# LCD-BackPack_v11.net
KiCad netlist of a schematic drawn in EAGLE
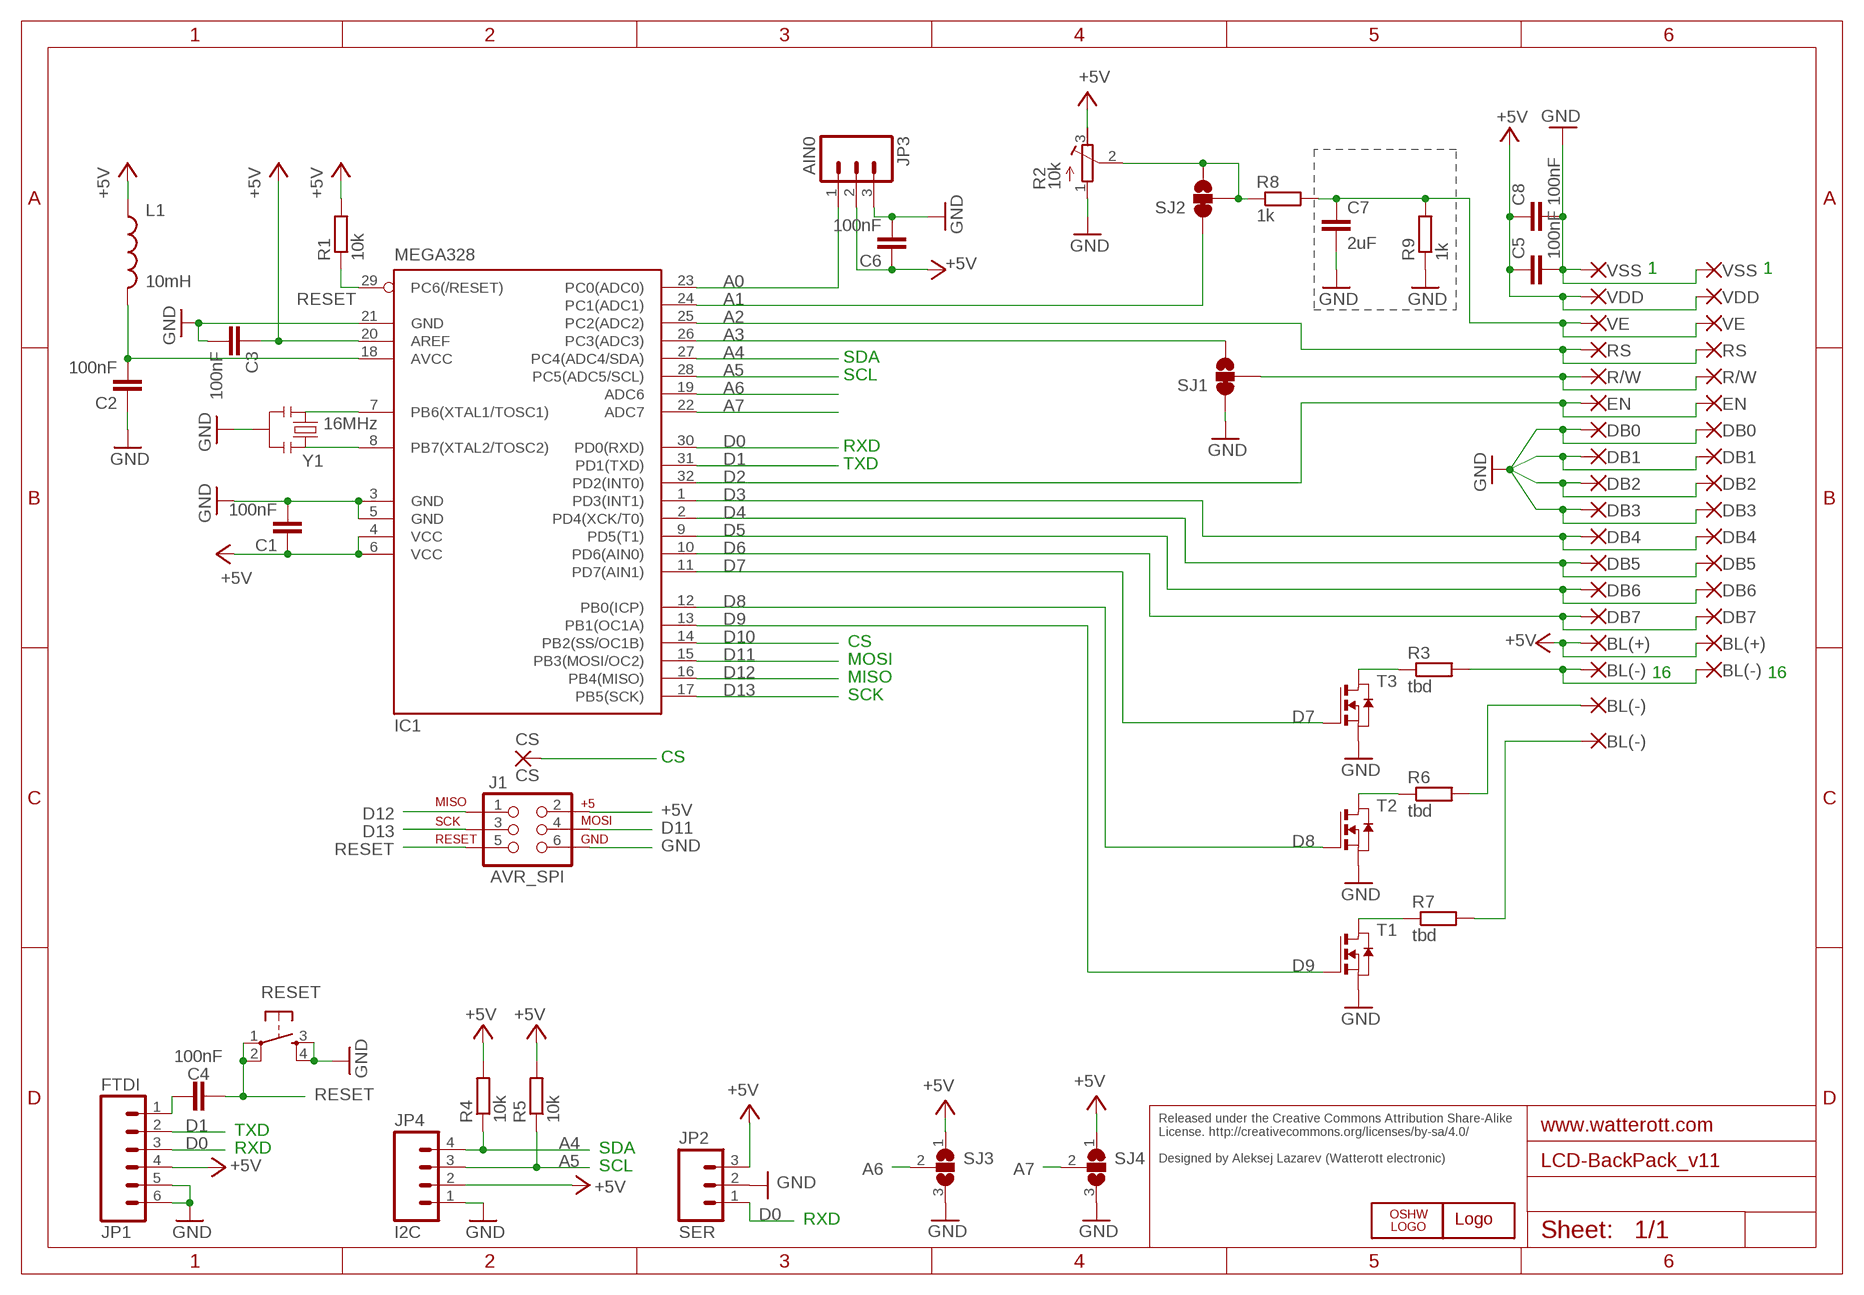
[diagram p0: schematic, sheet 1]

(export (version "E")
  (design (tool "Eeschema 10.0.6"))
  (components
    (comp (ref "C1")
      (value "100nF")
      (footprint "eagle-import:C0603")
      (libsource (lib "eagle-import") (part "C-EUC0603"))
    )
    (comp (ref "C2")
      (value "100nF")
      (footprint "eagle-import:C0603")
      (libsource (lib "eagle-import") (part "C-EUC0603"))
    )
    (comp (ref "C3")
      (value "100nF")
      (footprint "eagle-import:C0603")
      (libsource (lib "eagle-import") (part "C-EUC0603"))
    )
    (comp (ref "C4")
      (value "100nF")
      (footprint "eagle-import:C0603")
      (libsource (lib "eagle-import") (part "C-EUC0603"))
    )
    (comp (ref "C5")
      (value "100nF")
      (footprint "eagle-import:C0603")
      (libsource (lib "eagle-import") (part "C-EUC0603"))
    )
    (comp (ref "C6")
      (value "100nF")
      (footprint "eagle-import:C0603")
      (libsource (lib "eagle-import") (part "C-EUC0603"))
    )
    (comp (ref "C7")
      (value "2uF")
      (footprint "eagle-import:C0603")
      (libsource (lib "eagle-import") (part "C-EUC0603"))
    )
    (comp (ref "C8")
      (value "100nF")
      (footprint "eagle-import:C0603")
      (libsource (lib "eagle-import") (part "C-EUC0603"))
    )
    (comp (ref "CS")
      (value "CS")
      (footprint "eagle-import:1,6_0,9")
      (libsource (lib "eagle-import") (part "1,6/0,9"))
    )
    (comp (ref "IC1")
      (value "MEGA328")
      (footprint "eagle-import:TQFP32-08")
      (fields (field (name "MPN") "ATMEGA8-16AU"))
      (libsource (lib "eagle-import") (part "MEGA8-AI"))
    )
    (comp (ref "J1")
      (value "AVR_SPI")
      (footprint "eagle-import:2X3")
      (libsource (lib "eagle-import") (part "AVR_SPI_PRG_6PTH"))
    )
    (comp (ref "JP1")
      (value "FTDI")
      (footprint "eagle-import:1X06")
      (libsource (lib "eagle-import") (part "M06SIP"))
    )
    (comp (ref "JP2")
      (value "SER")
      (footprint "eagle-import:1X03")
      (libsource (lib "eagle-import") (part "M03PTH"))
    )
    (comp (ref "JP3")
      (value "AIN0")
      (footprint "eagle-import:1X03")
      (libsource (lib "eagle-import") (part "M03PTH"))
    )
    (comp (ref "JP4")
      (value "I2C")
      (footprint "eagle-import:1X04")
      (libsource (lib "eagle-import") (part "M04PTH"))
    )
    (comp (ref "L1")
      (value "10mH")
      (footprint "eagle-import:0603")
      (libsource (lib "eagle-import") (part "INDUCTOR30OHM,1.8A"))
    )
    (comp (ref "LOGO1")
      (value "OSHW_LOGO_6MILX0150-NT")
      (footprint "eagle-import:OSHW_6X150_NOTEXT")
      (libsource (lib "eagle-import") (part "OSHW_LOGO_6MILX0150-NT"))
    )
    (comp (ref "P1")
      (value "VSS")
      (footprint "eagle-import:1,6_0,9")
      (libsource (lib "eagle-import") (part "1,6/0,9"))
    )
    (comp (ref "P2")
      (value "VDD")
      (footprint "eagle-import:1,6_0,9")
      (libsource (lib "eagle-import") (part "1,6/0,9"))
    )
    (comp (ref "P3")
      (value "VE")
      (footprint "eagle-import:1,6_0,9")
      (libsource (lib "eagle-import") (part "1,6/0,9"))
    )
    (comp (ref "P4")
      (value "RS")
      (footprint "eagle-import:1,6_0,9")
      (libsource (lib "eagle-import") (part "1,6/0,9"))
    )
    (comp (ref "P5")
      (value "R/W")
      (footprint "eagle-import:1,6_0,9")
      (libsource (lib "eagle-import") (part "1,6/0,9"))
    )
    (comp (ref "P6")
      (value "EN")
      (footprint "eagle-import:1,6_0,9")
      (libsource (lib "eagle-import") (part "1,6/0,9"))
    )
    (comp (ref "P7")
      (value "DB0")
      (footprint "eagle-import:1,6_0,9")
      (libsource (lib "eagle-import") (part "1,6/0,9"))
    )
    (comp (ref "P8")
      (value "DB1")
      (footprint "eagle-import:1,6_0,9")
      (libsource (lib "eagle-import") (part "1,6/0,9"))
    )
    (comp (ref "P9")
      (value "DB2")
      (footprint "eagle-import:1,6_0,9")
      (libsource (lib "eagle-import") (part "1,6/0,9"))
    )
    (comp (ref "P10")
      (value "DB3")
      (footprint "eagle-import:1,6_0,9")
      (libsource (lib "eagle-import") (part "1,6/0,9"))
    )
    (comp (ref "P11")
      (value "DB4")
      (footprint "eagle-import:1,6_0,9")
      (libsource (lib "eagle-import") (part "1,6/0,9"))
    )
    (comp (ref "P12")
      (value "DB5")
      (footprint "eagle-import:1,6_0,9")
      (libsource (lib "eagle-import") (part "1,6/0,9"))
    )
    (comp (ref "P13")
      (value "DB6")
      (footprint "eagle-import:1,6_0,9")
      (libsource (lib "eagle-import") (part "1,6/0,9"))
    )
    (comp (ref "P14")
      (value "DB7")
      (footprint "eagle-import:1,6_0,9")
      (libsource (lib "eagle-import") (part "1,6/0,9"))
    )
    (comp (ref "P15")
      (value "BL(+)")
      (footprint "eagle-import:1,6_0,9")
      (libsource (lib "eagle-import") (part "1,6/0,9"))
    )
    (comp (ref "P16")
      (value "BL(-)")
      (footprint "eagle-import:1,6_0,9")
      (libsource (lib "eagle-import") (part "1,6/0,9"))
    )
    (comp (ref "P17")
      (value "BL(-)")
      (footprint "eagle-import:1,6_0,9")
      (libsource (lib "eagle-import") (part "1,6/0,9"))
    )
    (comp (ref "P18")
      (value "BL(-)")
      (footprint "eagle-import:1,6_0,9")
      (libsource (lib "eagle-import") (part "1,6/0,9"))
    )
    (comp (ref "P19")
      (value "VSS")
      (footprint "eagle-import:1,6_0,9")
      (libsource (lib "eagle-import") (part "1,6/0,9"))
    )
    (comp (ref "P20")
      (value "VDD")
      (footprint "eagle-import:1,6_0,9")
      (libsource (lib "eagle-import") (part "1,6/0,9"))
    )
    (comp (ref "P21")
      (value "VE")
      (footprint "eagle-import:1,6_0,9")
      (libsource (lib "eagle-import") (part "1,6/0,9"))
    )
    (comp (ref "P22")
      (value "RS")
      (footprint "eagle-import:1,6_0,9")
      (libsource (lib "eagle-import") (part "1,6/0,9"))
    )
    (comp (ref "P23")
      (value "R/W")
      (footprint "eagle-import:1,6_0,9")
      (libsource (lib "eagle-import") (part "1,6/0,9"))
    )
    (comp (ref "P24")
      (value "EN")
      (footprint "eagle-import:1,6_0,9")
      (libsource (lib "eagle-import") (part "1,6/0,9"))
    )
    (comp (ref "P25")
      (value "DB0")
      (footprint "eagle-import:1,6_0,9")
      (libsource (lib "eagle-import") (part "1,6/0,9"))
    )
    (comp (ref "P26")
      (value "DB1")
      (footprint "eagle-import:1,6_0,9")
      (libsource (lib "eagle-import") (part "1,6/0,9"))
    )
    (comp (ref "P27")
      (value "DB2")
      (footprint "eagle-import:1,6_0,9")
      (libsource (lib "eagle-import") (part "1,6/0,9"))
    )
    (comp (ref "P28")
      (value "DB3")
      (footprint "eagle-import:1,6_0,9")
      (libsource (lib "eagle-import") (part "1,6/0,9"))
    )
    (comp (ref "P29")
      (value "DB4")
      (footprint "eagle-import:1,6_0,9")
      (libsource (lib "eagle-import") (part "1,6/0,9"))
    )
    (comp (ref "P30")
      (value "DB5")
      (footprint "eagle-import:1,6_0,9")
      (libsource (lib "eagle-import") (part "1,6/0,9"))
    )
    (comp (ref "P31")
      (value "DB6")
      (footprint "eagle-import:1,6_0,9")
      (libsource (lib "eagle-import") (part "1,6/0,9"))
    )
    (comp (ref "P32")
      (value "DB7")
      (footprint "eagle-import:1,6_0,9")
      (libsource (lib "eagle-import") (part "1,6/0,9"))
    )
    (comp (ref "P33")
      (value "BL(+)")
      (footprint "eagle-import:1,6_0,9")
      (libsource (lib "eagle-import") (part "1,6/0,9"))
    )
    (comp (ref "P34")
      (value "BL(-)")
      (footprint "eagle-import:1,6_0,9")
      (libsource (lib "eagle-import") (part "1,6/0,9"))
    )
    (comp (ref "R1")
      (value "10k")
      (footprint "eagle-import:R0603")
      (libsource (lib "eagle-import") (part "R-EU_R0603"))
    )
    (comp (ref "R2")
      (value "10k")
      (footprint "eagle-import:RTRIM3374")
      (libsource (lib "eagle-import") (part "R-TRIMM3374"))
    )
    (comp (ref "R3")
      (value "tbd")
      (footprint "eagle-import:R0603")
      (libsource (lib "eagle-import") (part "R-EU_R0603"))
    )
    (comp (ref "R4")
      (value "10k")
      (footprint "eagle-import:R0603")
      (libsource (lib "eagle-import") (part "R-EU_R0603"))
    )
    (comp (ref "R5")
      (value "10k")
      (footprint "eagle-import:R0603")
      (libsource (lib "eagle-import") (part "R-EU_R0603"))
    )
    (comp (ref "R6")
      (value "tbd")
      (footprint "eagle-import:R0603")
      (libsource (lib "eagle-import") (part "R-EU_R0603"))
    )
    (comp (ref "R7")
      (value "tbd")
      (footprint "eagle-import:R0603")
      (libsource (lib "eagle-import") (part "R-EU_R0603"))
    )
    (comp (ref "R8")
      (value "1k")
      (footprint "eagle-import:R0603")
      (libsource (lib "eagle-import") (part "R-EU_R0603"))
    )
    (comp (ref "R9")
      (value "1k")
      (footprint "eagle-import:R0603")
      (libsource (lib "eagle-import") (part "R-EU_R0603"))
    )
    (comp (ref "RESET")
      (value "TAC_SWITCHSMD")
      (footprint "eagle-import:TACTILE_SWITCH_SMD")
      (libsource (lib "eagle-import") (part "TAC_SWITCHSMD"))
    )
    (comp (ref "SJ1")
      (value "SOLDERJUMPER_2WAY-OLDS")
      (footprint "eagle-import:SJ_3")
      (libsource (lib "eagle-import") (part "SOLDERJUMPER_2WAY-OLDS"))
    )
    (comp (ref "SJ2")
      (value "SOLDERJUMPER_2WAY-OLDS")
      (footprint "eagle-import:SJ_3")
      (libsource (lib "eagle-import") (part "SOLDERJUMPER_2WAY-OLDS"))
    )
    (comp (ref "SJ3")
      (value "SJ2W")
      (footprint "eagle-import:SJ_2")
      (libsource (lib "eagle-import") (part "SJ2W"))
    )
    (comp (ref "SJ4")
      (value "SJ2W")
      (footprint "eagle-import:SJ_2")
      (libsource (lib "eagle-import") (part "SJ2W"))
    )
    (comp (ref "T1")
      (value "NMOSSOT23")
      (footprint "eagle-import:SOT-23")
      (libsource (lib "eagle-import") (part "NMOSSOT23"))
    )
    (comp (ref "T2")
      (value "NMOSSOT23")
      (footprint "eagle-import:SOT-23")
      (libsource (lib "eagle-import") (part "NMOSSOT23"))
    )
    (comp (ref "T3")
      (value "NMOSSOT23")
      (footprint "eagle-import:SOT-23")
      (libsource (lib "eagle-import") (part "NMOSSOT23"))
    )
    (comp (ref "U$1")
      (value "WE-LOGO")
      (footprint "eagle-import:WE-LOGO")
      (libsource (lib "eagle-import") (part "WE-LOGOPLACE"))
    )
    (comp (ref "Y1")
      (value "16MHz")
      (footprint "eagle-import:RESONATOR-SMD")
      (libsource (lib "eagle-import") (part "RESONATOR16MHZ"))
    )
  )
  (nets
    (net (code "1") (name "+5V") (class "Default")
      (node (ref "C1") (pin "1") (pinfunction "1_1") (pintype "passive"))
      (node (ref "C3") (pin "1") (pinfunction "1_1") (pintype "passive"))
      (node (ref "C5") (pin "1") (pinfunction "1_1") (pintype "passive"))
      (node (ref "C6") (pin "1") (pinfunction "1_1") (pintype "passive"))
      (node (ref "C8") (pin "1") (pinfunction "1_1") (pintype "passive"))
      (node (ref "IC1") (pin "20") (pinfunction "AREF_20") (pintype "passive"))
      (node (ref "IC1") (pin "4") (pinfunction "VCC_4") (pintype "power_in"))
      (node (ref "IC1") (pin "6") (pinfunction "VCC_6") (pintype "power_in"))
      (node (ref "J1") (pin "2") (pinfunction "2_2") (pintype "passive"))
      (node (ref "JP1") (pin "4") (pinfunction "4_4") (pintype "passive"))
      (node (ref "JP2") (pin "3") (pinfunction "3_3") (pintype "passive"))
      (node (ref "JP3") (pin "2") (pinfunction "2_2") (pintype "passive"))
      (node (ref "JP4") (pin "2") (pinfunction "2_2") (pintype "passive"))
      (node (ref "L1") (pin "1") (pinfunction "1_1") (pintype "passive"))
      (node (ref "P15") (pin "1") (pinfunction "P_1") (pintype "passive"))
      (node (ref "P2") (pin "1") (pinfunction "P_1") (pintype "passive"))
      (node (ref "P20") (pin "1") (pinfunction "P_1") (pintype "passive"))
      (node (ref "P33") (pin "1") (pinfunction "P_1") (pintype "passive"))
      (node (ref "R1") (pin "2") (pinfunction "2_2") (pintype "passive"))
      (node (ref "R2") (pin "3") (pinfunction "A_3") (pintype "passive"))
      (node (ref "R4") (pin "2") (pinfunction "2_2") (pintype "passive"))
      (node (ref "R5") (pin "2") (pinfunction "2_2") (pintype "passive"))
      (node (ref "SJ3") (pin "1") (pinfunction "1_1") (pintype "passive"))
      (node (ref "SJ4") (pin "1") (pinfunction "1_1") (pintype "passive"))
    )
    (net (code "2") (name "/A0") (class "Default")
      (node (ref "IC1") (pin "23") (pinfunction "PC0(ADC0)_23") (pintype "bidirectional"))
      (node (ref "JP3") (pin "1") (pinfunction "1_1") (pintype "passive"))
    )
    (net (code "3") (name "/A1") (class "Default")
      (node (ref "IC1") (pin "24") (pinfunction "PC1(ADC1)_24") (pintype "bidirectional"))
      (node (ref "SJ2") (pin "1") (pinfunction "1_1") (pintype "passive"))
    )
    (net (code "4") (name "/A2") (class "Default")
      (node (ref "IC1") (pin "25") (pinfunction "PC2(ADC2)_25") (pintype "bidirectional"))
      (node (ref "P22") (pin "1") (pinfunction "P_1") (pintype "passive"))
      (node (ref "P4") (pin "1") (pinfunction "P_1") (pintype "passive"))
    )
    (net (code "5") (name "/A3") (class "Default")
      (node (ref "IC1") (pin "26") (pinfunction "PC3(ADC3)_26") (pintype "bidirectional"))
      (node (ref "SJ1") (pin "3") (pinfunction "3_3") (pintype "passive"))
    )
    (net (code "6") (name "/A4") (class "Default")
      (node (ref "IC1") (pin "27") (pinfunction "PC4(ADC4/SDA)_27") (pintype "bidirectional"))
      (node (ref "JP4") (pin "4") (pinfunction "4_4") (pintype "passive"))
      (node (ref "R4") (pin "1") (pinfunction "1_1") (pintype "passive"))
    )
    (net (code "7") (name "/A5") (class "Default")
      (node (ref "IC1") (pin "28") (pinfunction "PC5(ADC5/SCL)_28") (pintype "bidirectional"))
      (node (ref "JP4") (pin "3") (pinfunction "3_3") (pintype "passive"))
      (node (ref "R5") (pin "1") (pinfunction "1_1") (pintype "passive"))
    )
    (net (code "8") (name "/A6") (class "Default")
      (node (ref "IC1") (pin "19") (pinfunction "ADC6_19") (pintype "bidirectional"))
      (node (ref "SJ3") (pin "2") (pinfunction "2_2") (pintype "passive"))
    )
    (net (code "9") (name "/A7") (class "Default")
      (node (ref "IC1") (pin "22") (pinfunction "ADC7_22") (pintype "bidirectional"))
      (node (ref "SJ4") (pin "2") (pinfunction "2_2") (pintype "passive"))
    )
    (net (code "10") (name "/D0") (class "Default")
      (node (ref "IC1") (pin "30") (pinfunction "PD0(RXD)_30") (pintype "bidirectional"))
      (node (ref "JP1") (pin "3") (pinfunction "3_3") (pintype "passive"))
      (node (ref "JP2") (pin "1") (pinfunction "1_1") (pintype "passive"))
    )
    (net (code "11") (name "/D1") (class "Default")
      (node (ref "IC1") (pin "31") (pinfunction "PD1(TXD)_31") (pintype "bidirectional"))
      (node (ref "JP1") (pin "2") (pinfunction "2_2") (pintype "passive"))
    )
    (net (code "12") (name "/D2") (class "Default")
      (node (ref "IC1") (pin "32") (pinfunction "PD2(INT0)_32") (pintype "bidirectional"))
      (node (ref "P24") (pin "1") (pinfunction "P_1") (pintype "passive"))
      (node (ref "P6") (pin "1") (pinfunction "P_1") (pintype "passive"))
    )
    (net (code "13") (name "/D3") (class "Default")
      (node (ref "IC1") (pin "1") (pinfunction "PD3(INT1)_1") (pintype "bidirectional"))
      (node (ref "P11") (pin "1") (pinfunction "P_1") (pintype "passive"))
      (node (ref "P29") (pin "1") (pinfunction "P_1") (pintype "passive"))
    )
    (net (code "14") (name "/D4") (class "Default")
      (node (ref "IC1") (pin "2") (pinfunction "PD4(XCK/T0)_2") (pintype "bidirectional"))
      (node (ref "P12") (pin "1") (pinfunction "P_1") (pintype "passive"))
      (node (ref "P30") (pin "1") (pinfunction "P_1") (pintype "passive"))
    )
    (net (code "15") (name "/D5") (class "Default")
      (node (ref "IC1") (pin "9") (pinfunction "PD5(T1)_9") (pintype "bidirectional"))
      (node (ref "P13") (pin "1") (pinfunction "P_1") (pintype "passive"))
      (node (ref "P31") (pin "1") (pinfunction "P_1") (pintype "passive"))
    )
    (net (code "16") (name "/D6") (class "Default")
      (node (ref "IC1") (pin "10") (pinfunction "PD6(AIN0)_10") (pintype "bidirectional"))
      (node (ref "P14") (pin "1") (pinfunction "P_1") (pintype "passive"))
      (node (ref "P32") (pin "1") (pinfunction "P_1") (pintype "passive"))
    )
    (net (code "17") (name "/D7") (class "Default")
      (node (ref "IC1") (pin "11") (pinfunction "PD7(AIN1)_11") (pintype "bidirectional"))
      (node (ref "T3") (pin "3") (pinfunction "G_3") (pintype "passive"))
    )
    (net (code "18") (name "/D8") (class "Default")
      (node (ref "IC1") (pin "12") (pinfunction "PB0(ICP)_12") (pintype "bidirectional"))
      (node (ref "T2") (pin "3") (pinfunction "G_3") (pintype "passive"))
    )
    (net (code "19") (name "/D9") (class "Default")
      (node (ref "IC1") (pin "13") (pinfunction "PB1(OC1A)_13") (pintype "bidirectional"))
      (node (ref "T1") (pin "3") (pinfunction "G_3") (pintype "passive"))
    )
    (net (code "20") (name "/D10") (class "Default")
      (node (ref "CS") (pin "1") (pinfunction "P_1") (pintype "passive"))
      (node (ref "IC1") (pin "14") (pinfunction "PB2(SS/OC1B)_14") (pintype "bidirectional"))
    )
    (net (code "21") (name "/D11") (class "Default")
      (node (ref "IC1") (pin "15") (pinfunction "PB3(MOSI/OC2)_15") (pintype "bidirectional"))
      (node (ref "J1") (pin "4") (pinfunction "4_4") (pintype "passive"))
    )
    (net (code "22") (name "/D12") (class "Default")
      (node (ref "IC1") (pin "16") (pinfunction "PB4(MISO)_16") (pintype "bidirectional"))
      (node (ref "J1") (pin "1") (pinfunction "1_1") (pintype "passive"))
    )
    (net (code "23") (name "/D13") (class "Default")
      (node (ref "IC1") (pin "17") (pinfunction "PB5(SCK)_17") (pintype "bidirectional"))
      (node (ref "J1") (pin "3") (pinfunction "3_3") (pintype "passive"))
    )
    (net (code "24") (name "/RESET") (class "Default")
      (node (ref "C4") (pin "1") (pinfunction "1_1") (pintype "passive"))
      (node (ref "IC1") (pin "29") (pinfunction "PC6(/RESET)_29") (pintype "bidirectional"))
      (node (ref "J1") (pin "5") (pinfunction "5_5") (pintype "passive"))
      (node (ref "R1") (pin "1") (pinfunction "1_1") (pintype "passive"))
      (node (ref "RESET") (pin "1") (pinfunction "1_1") (pintype "passive"))
      (node (ref "RESET") (pin "2") (pinfunction "2_2") (pintype "passive"))
    )
    (net (code "25") (name "GND") (class "Default")
      (node (ref "C1") (pin "2") (pinfunction "2_2") (pintype "passive"))
      (node (ref "C2") (pin "1") (pinfunction "1_1") (pintype "passive"))
      (node (ref "C3") (pin "2") (pinfunction "2_2") (pintype "passive"))
      (node (ref "C5") (pin "2") (pinfunction "2_2") (pintype "passive"))
      (node (ref "C6") (pin "2") (pinfunction "2_2") (pintype "passive"))
      (node (ref "C7") (pin "2") (pinfunction "2_2") (pintype "passive"))
      (node (ref "C8") (pin "2") (pinfunction "2_2") (pintype "passive"))
      (node (ref "IC1") (pin "21") (pinfunction "GND_21") (pintype "power_in"))
      (node (ref "IC1") (pin "3") (pinfunction "GND_3") (pintype "power_in"))
      (node (ref "IC1") (pin "5") (pinfunction "GND_5") (pintype "power_in"))
      (node (ref "J1") (pin "6") (pinfunction "6_6") (pintype "passive"))
      (node (ref "JP1") (pin "5") (pinfunction "5_5") (pintype "passive"))
      (node (ref "JP1") (pin "6") (pinfunction "6_6") (pintype "passive"))
      (node (ref "JP2") (pin "2") (pinfunction "2_2") (pintype "passive"))
      (node (ref "JP3") (pin "3") (pinfunction "3_3") (pintype "passive"))
      (node (ref "JP4") (pin "1") (pinfunction "1_1") (pintype "passive"))
      (node (ref "P1") (pin "1") (pinfunction "P_1") (pintype "passive"))
      (node (ref "P10") (pin "1") (pinfunction "P_1") (pintype "passive"))
      (node (ref "P19") (pin "1") (pinfunction "P_1") (pintype "passive"))
      (node (ref "P25") (pin "1") (pinfunction "P_1") (pintype "passive"))
      (node (ref "P26") (pin "1") (pinfunction "P_1") (pintype "passive"))
      (node (ref "P27") (pin "1") (pinfunction "P_1") (pintype "passive"))
      (node (ref "P28") (pin "1") (pinfunction "P_1") (pintype "passive"))
      (node (ref "P7") (pin "1") (pinfunction "P_1") (pintype "passive"))
      (node (ref "P8") (pin "1") (pinfunction "P_1") (pintype "passive"))
      (node (ref "P9") (pin "1") (pinfunction "P_1") (pintype "passive"))
      (node (ref "R2") (pin "1") (pinfunction "E_1") (pintype "passive"))
      (node (ref "R9") (pin "1") (pinfunction "1_1") (pintype "passive"))
      (node (ref "RESET") (pin "3") (pinfunction "3_3") (pintype "passive"))
      (node (ref "RESET") (pin "4") (pinfunction "4_4") (pintype "passive"))
      (node (ref "SJ1") (pin "1") (pinfunction "1_1") (pintype "passive"))
      (node (ref "SJ3") (pin "3") (pinfunction "3_3") (pintype "passive"))
      (node (ref "SJ4") (pin "3") (pinfunction "3_3") (pintype "passive"))
      (node (ref "T1") (pin "2") (pinfunction "S_2") (pintype "passive"))
      (node (ref "T2") (pin "2") (pinfunction "S_2") (pintype "passive"))
      (node (ref "T3") (pin "2") (pinfunction "S_2") (pintype "passive"))
      (node (ref "Y1") (pin "2") (pinfunction "2_2") (pintype "passive"))
    )
    (net (code "26") (name "Net-(C4-Pad2)") (class "Default")
      (node (ref "C4") (pin "2") (pinfunction "2_2") (pintype "passive"))
      (node (ref "JP1") (pin "1") (pinfunction "1_1") (pintype "passive"))
    )
    (net (code "27") (name "Net-(IC1-AVCC)") (class "Default")
      (node (ref "C2") (pin "2") (pinfunction "2_2") (pintype "passive"))
      (node (ref "IC1") (pin "18") (pinfunction "AVCC_18") (pintype "power_in"))
      (node (ref "L1") (pin "2") (pinfunction "2_2") (pintype "passive"))
    )
    (net (code "28") (name "Net-(IC1-PB6(XTAL1{slash}TOSC1))") (class "Default")
      (node (ref "IC1") (pin "7") (pinfunction "PB6(XTAL1/TOSC1)_7") (pintype "bidirectional"))
      (node (ref "Y1") (pin "1") (pinfunction "1_1") (pintype "passive"))
    )
    (net (code "29") (name "Net-(IC1-PB7(XTAL2{slash}TOSC2))") (class "Default")
      (node (ref "IC1") (pin "8") (pinfunction "PB7(XTAL2/TOSC2)_8") (pintype "bidirectional"))
      (node (ref "Y1") (pin "3") (pinfunction "3_3") (pintype "passive"))
    )
    (net (code "30") (name "Net-(P16-P)") (class "Default")
      (node (ref "P16") (pin "1") (pinfunction "P_1") (pintype "passive"))
      (node (ref "P34") (pin "1") (pinfunction "P_1") (pintype "passive"))
      (node (ref "R3") (pin "2") (pinfunction "2_2") (pintype "passive"))
    )
    (net (code "31") (name "Net-(P17-P)") (class "Default")
      (node (ref "P17") (pin "1") (pinfunction "P_1") (pintype "passive"))
      (node (ref "R6") (pin "2") (pinfunction "2_2") (pintype "passive"))
    )
    (net (code "32") (name "Net-(P18-P)") (class "Default")
      (node (ref "P18") (pin "1") (pinfunction "P_1") (pintype "passive"))
      (node (ref "R7") (pin "2") (pinfunction "2_2") (pintype "passive"))
    )
    (net (code "33") (name "Net-(P21-P)") (class "Default")
      (node (ref "C7") (pin "1") (pinfunction "1_1") (pintype "passive"))
      (node (ref "P21") (pin "1") (pinfunction "P_1") (pintype "passive"))
      (node (ref "P3") (pin "1") (pinfunction "P_1") (pintype "passive"))
      (node (ref "R8") (pin "2") (pinfunction "2_2") (pintype "passive"))
      (node (ref "R9") (pin "2") (pinfunction "2_2") (pintype "passive"))
    )
    (net (code "34") (name "Net-(P23-P)") (class "Default")
      (node (ref "P23") (pin "1") (pinfunction "P_1") (pintype "passive"))
      (node (ref "P5") (pin "1") (pinfunction "P_1") (pintype "passive"))
      (node (ref "SJ1") (pin "2") (pinfunction "2_2") (pintype "passive"))
    )
    (net (code "35") (name "Net-(R2-S)") (class "Default")
      (node (ref "R2") (pin "2") (pinfunction "S_2") (pintype "passive"))
      (node (ref "R8") (pin "1") (pinfunction "1_1") (pintype "passive"))
      (node (ref "SJ2") (pin "2") (pinfunction "2_2") (pintype "passive"))
      (node (ref "SJ2") (pin "3") (pinfunction "3_3") (pintype "passive"))
    )
    (net (code "36") (name "Net-(T1-D)") (class "Default")
      (node (ref "R7") (pin "1") (pinfunction "1_1") (pintype "passive"))
      (node (ref "T1") (pin "1") (pinfunction "D_1") (pintype "passive"))
    )
    (net (code "37") (name "Net-(T2-D)") (class "Default")
      (node (ref "R6") (pin "1") (pinfunction "1_1") (pintype "passive"))
      (node (ref "T2") (pin "1") (pinfunction "D_1") (pintype "passive"))
    )
    (net (code "38") (name "Net-(T3-D)") (class "Default")
      (node (ref "R3") (pin "1") (pinfunction "1_1") (pintype "passive"))
      (node (ref "T3") (pin "1") (pinfunction "D_1") (pintype "passive"))
    )
  )
)
